# MSP_Telemetry.net
KiCad netlist of a schematic drawn in Altium Designer
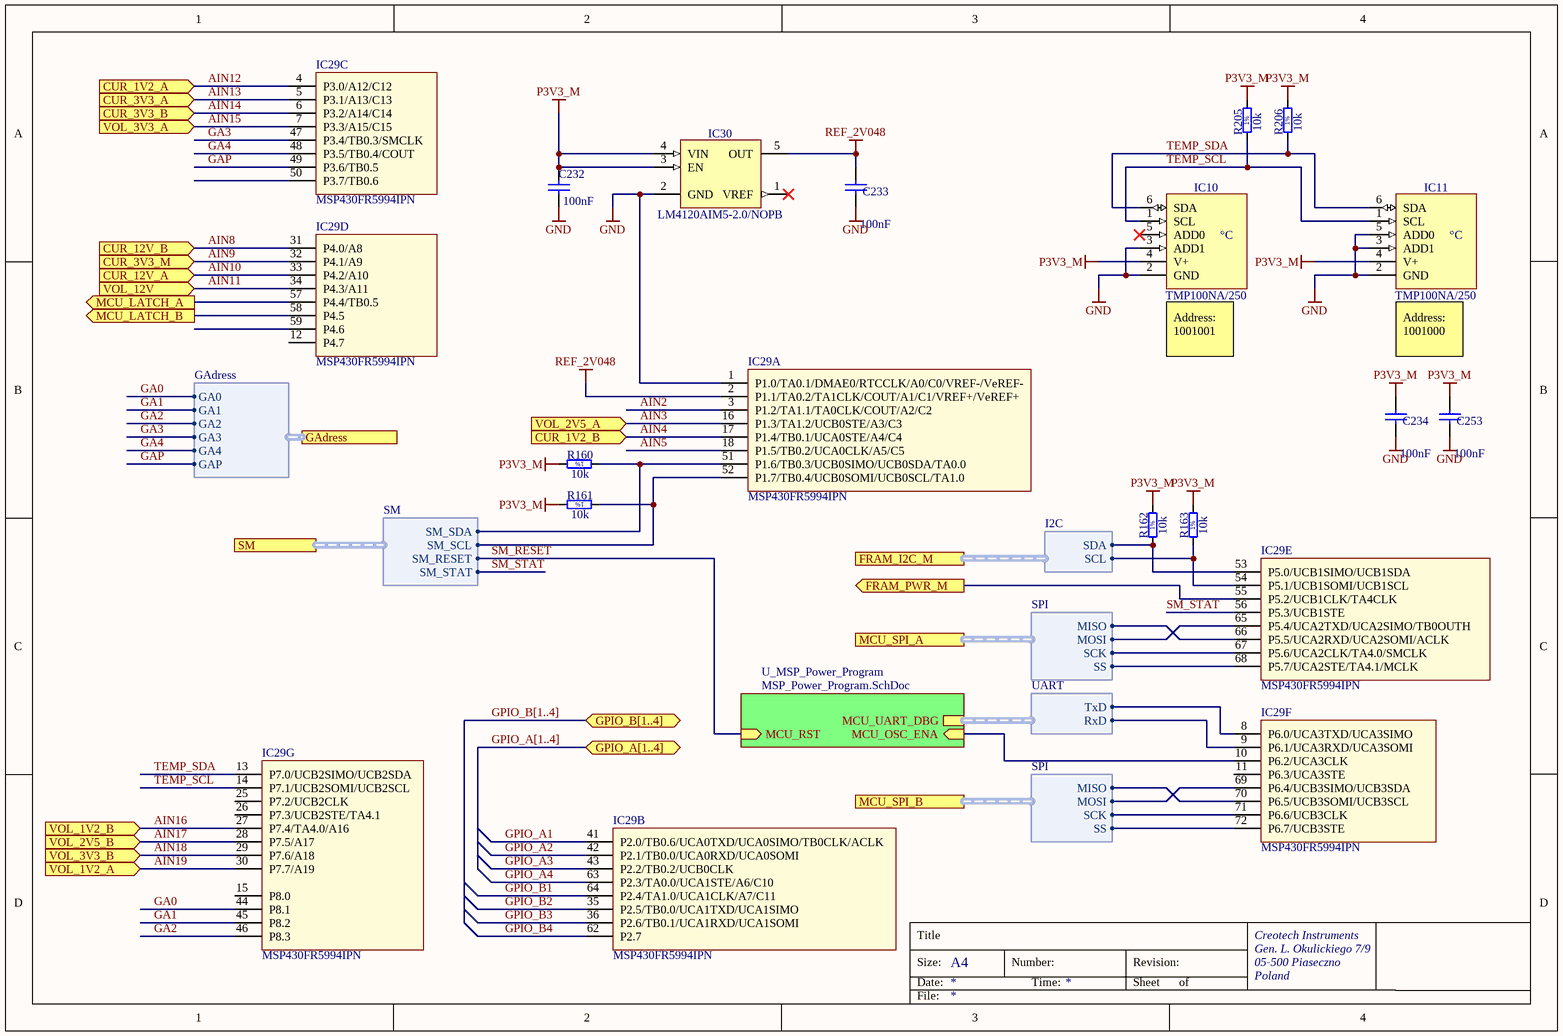
[diagram p0: MSP_Telemetry.SchDoc]

(export (version "E")
  (design (tool "Eeschema 10.0.6"))
  (components
    (comp (ref "C232")
      (value "100nF")
      (footprint "CAPC1608X87N")
      (description "Non-polarised capacitor")
      (fields
        (field (name "PART NUMBER") "CC0603_100NF_50V_10%_X7R")
        (field (name "VOLTAGE") "50V")
        (field (name "AUTHOR") "CERN DEM JLC")
      )
      (libsource (lib "Capacitors") (part "Capacitor - non polarized"))
    )
    (comp (ref "C233")
      (value "100nF")
      (footprint "CAPC1608X87N")
      (description "Non-polarised capacitor")
      (fields
        (field (name "PART NUMBER") "CC0603_100NF_50V_10%_X7R")
        (field (name "VOLTAGE") "50V")
        (field (name "AUTHOR") "CERN DEM JLC")
      )
      (libsource (lib "Capacitors") (part "Capacitor - non polarized"))
    )
    (comp (ref "C234")
      (value "100nF")
      (footprint "CAPC1608X87N")
      (description "Non-polarised capacitor")
      (fields
        (field (name "PART NUMBER") "CC0603_100NF_50V_10%_X7R")
        (field (name "VOLTAGE") "50V")
        (field (name "AUTHOR") "CERN DEM JLC")
      )
      (libsource (lib "Capacitors") (part "Capacitor - non polarized"))
    )
    (comp (ref "C253")
      (value "100nF")
      (footprint "CAPC1608X87N")
      (description "Non-polarised capacitor")
      (fields
        (field (name "PART NUMBER") "CC0603_100NF_50V_10%_X7R")
        (field (name "VOLTAGE") "50V")
        (field (name "AUTHOR") "CERN DEM JLC")
      )
      (libsource (lib "Capacitors") (part "Capacitor - non polarized"))
    )
    (comp (ref "IC10")
      (value "TMP100NA/250")
      (footprint "SOT95P280X145-6N")
      (description "Digital Temperature Sensor with I2C Interface")
      (fields (field (name "MANUFACTURER") "TEXAS INSTRUMENTS") (field (name "AUTHOR") "CERN DEM JLC"))
      (libsource (lib "ICs And Semiconductors") (part "TMP100"))
    )
    (comp (ref "IC11")
      (value "TMP100NA/250")
      (footprint "SOT95P280X145-6N")
      (description "Digital Temperature Sensor with I2C Interface")
      (fields (field (name "MANUFACTURER") "TEXAS INSTRUMENTS") (field (name "AUTHOR") "CERN DEM JLC"))
      (libsource (lib "ICs And Semiconductors") (part "TMP100"))
    )
    (comp (ref "IC29")
      (value "MSP430FR5994IPN")
      (footprint "PQFP50P1400X1400-80N")
      (fields (field (name "MANUFACTURER") "TI"))
      (libsource (lib "LIBRARY_SCH") (part "UPC_MSP430FR5994IPN"))
    )
    (comp (ref "IC30")
      (value "LM4120AIM5-2.0/NOPB")
      (footprint "SOT95P280X145-5N")
      (description "Precision Micropower Low Dropout Voltage Reference")
      (fields (field (name "MANUFACTURER") "TEXAS INSTRUMENTS") (field (name "AUTHOR") "CERN DEM JMW"))
      (libsource (lib "ICs And Semiconductors") (part "LM4120"))
    )
    (comp (ref "R160")
      (value "10k")
      (footprint "RESC1608X55N")
      (description "Resistor - 1%")
      (fields
        (field (name "PART NUMBER") "R0603_10K_1%_0.1W_100PPM")
        (field (name "POWER") "0.1W")
        (field (name "AUTHOR") "CERN DEM JLC")
      )
      (libsource (lib "Resistors") (part "Resistor - 1%"))
    )
    (comp (ref "R161")
      (value "10k")
      (footprint "RESC1608X55N")
      (description "Resistor - 1%")
      (fields
        (field (name "PART NUMBER") "R0603_10K_1%_0.1W_100PPM")
        (field (name "POWER") "0.1W")
        (field (name "AUTHOR") "CERN DEM JLC")
      )
      (libsource (lib "Resistors") (part "Resistor - 1%"))
    )
    (comp (ref "R162")
      (value "10k")
      (footprint "RESC1608X55N")
      (description "Resistor - 1%")
      (fields
        (field (name "PART NUMBER") "R0603_10K_1%_0.1W_100PPM")
        (field (name "POWER") "0.1W")
        (field (name "AUTHOR") "CERN DEM JLC")
      )
      (libsource (lib "Resistors") (part "Resistor - 1%"))
    )
    (comp (ref "R163")
      (value "10k")
      (footprint "RESC1608X55N")
      (description "Resistor - 1%")
      (fields
        (field (name "PART NUMBER") "R0603_10K_1%_0.1W_100PPM")
        (field (name "POWER") "0.1W")
        (field (name "AUTHOR") "CERN DEM JLC")
      )
      (libsource (lib "Resistors") (part "Resistor - 1%"))
    )
    (comp (ref "R205")
      (value "10k")
      (footprint "RESC1608X55N")
      (description "Resistor - 1%")
      (fields
        (field (name "PART NUMBER") "R0603_10K_1%_0.1W_100PPM")
        (field (name "POWER") "0.1W")
        (field (name "AUTHOR") "CERN DEM JLC")
      )
      (libsource (lib "Resistors") (part "Resistor - 1%"))
    )
    (comp (ref "R206")
      (value "10k")
      (footprint "RESC1608X55N")
      (description "Resistor - 1%")
      (fields
        (field (name "PART NUMBER") "R0603_10K_1%_0.1W_100PPM")
        (field (name "POWER") "0.1W")
        (field (name "AUTHOR") "CERN DEM JLC")
      )
      (libsource (lib "Resistors") (part "Resistor - 1%"))
    )
  )
  (nets
    (net (code "6") (name "/AIN2") (class "Default")
      (node (ref "IC29") (pin "3") (pinfunction "P1.2/TA1.1/TA0CLK/COUT/A2/C2_3") (pintype "passive"))
    )
    (net (code "7") (name "/AIN3") (class "Default")
      (node (ref "IC29") (pin "16") (pinfunction "P1.3/TA1.2/UCB0STE/A3/C3_16") (pintype "passive"))
    )
    (net (code "8") (name "/AIN4") (class "Default")
      (node (ref "IC29") (pin "17") (pinfunction "P1.4/TB0.1/UCA0STE/A4/C4_17") (pintype "passive"))
    )
    (net (code "9") (name "/AIN5") (class "Default")
      (node (ref "IC29") (pin "18") (pinfunction "P1.5/TB0.2/UCA0CLK/A5/C5_18") (pintype "passive"))
    )
    (net (code "10") (name "/AIN8") (class "Default")
      (node (ref "IC29") (pin "31") (pinfunction "P4.0/A8_31") (pintype "passive"))
    )
    (net (code "11") (name "/AIN9") (class "Default")
      (node (ref "IC29") (pin "32") (pinfunction "P4.1/A9_32") (pintype "passive"))
    )
    (net (code "12") (name "/AIN10") (class "Default")
      (node (ref "IC29") (pin "33") (pinfunction "P4.2/A10_33") (pintype "passive"))
    )
    (net (code "13") (name "/AIN11") (class "Default")
      (node (ref "IC29") (pin "34") (pinfunction "P4.3/A11_34") (pintype "passive"))
    )
    (net (code "14") (name "/AIN12") (class "Default")
      (node (ref "IC29") (pin "4") (pinfunction "P3.0/A12/C12_4") (pintype "passive"))
    )
    (net (code "15") (name "/AIN13") (class "Default")
      (node (ref "IC29") (pin "5") (pinfunction "P3.1/A13/C13_5") (pintype "passive"))
    )
    (net (code "16") (name "/AIN14") (class "Default")
      (node (ref "IC29") (pin "6") (pinfunction "P3.2/A14/C14_6") (pintype "passive"))
    )
    (net (code "17") (name "/AIN15") (class "Default")
      (node (ref "IC29") (pin "7") (pinfunction "P3.3/A15/C15_7") (pintype "passive"))
    )
    (net (code "18") (name "/AIN16") (class "Default")
      (node (ref "IC29") (pin "27") (pinfunction "P7.4/TA4.0/A16_27") (pintype "passive"))
    )
    (net (code "19") (name "/AIN17") (class "Default")
      (node (ref "IC29") (pin "28") (pinfunction "P7.5/A17_28") (pintype "passive"))
    )
    (net (code "20") (name "/AIN18") (class "Default")
      (node (ref "IC29") (pin "29") (pinfunction "P7.6/A18_29") (pintype "passive"))
    )
    (net (code "21") (name "/AIN19") (class "Default")
      (node (ref "IC29") (pin "30") (pinfunction "P7.7/A19_30") (pintype "passive"))
    )
    (net (code "22") (name "/FRAM_PWR_M") (class "Default")
      (node (ref "IC29") (pin "55") (pinfunction "P5.2/UCB1CLK/TA4CLK_55") (pintype "passive"))
    )
    (net (code "23") (name "/GA0") (class "Default")
      (node (ref "IC29") (pin "44") (pinfunction "P8.1_44") (pintype "passive"))
    )
    (net (code "24") (name "/GA1") (class "Default")
      (node (ref "IC29") (pin "45") (pinfunction "P8.2_45") (pintype "passive"))
    )
    (net (code "25") (name "/GA2") (class "Default")
      (node (ref "IC29") (pin "46") (pinfunction "P8.3_46") (pintype "passive"))
    )
    (net (code "26") (name "/GA3") (class "Default")
      (node (ref "IC29") (pin "47") (pinfunction "P3.4/TB0.3/SMCLK_47") (pintype "passive"))
    )
    (net (code "27") (name "/GA4") (class "Default")
      (node (ref "IC29") (pin "48") (pinfunction "P3.5/TB0.4/COUT_48") (pintype "passive"))
    )
    (net (code "28") (name "/GAP") (class "Default")
      (node (ref "IC29") (pin "49") (pinfunction "P3.6/TB0.5_49") (pintype "passive"))
    )
    (net (code "29") (name "/GPIO_A1") (class "Default")
      (node (ref "IC29") (pin "41") (pinfunction "P2.0/TB0.6/UCA0TXD/UCA0SIMO/TB0CLK/ACLK_41") (pintype "passive"))
    )
    (net (code "30") (name "/GPIO_A2") (class "Default")
      (node (ref "IC29") (pin "42") (pinfunction "P2.1/TB0.0/UCA0RXD/UCA0SOMI_42") (pintype "passive"))
    )
    (net (code "31") (name "/GPIO_A3") (class "Default")
      (node (ref "IC29") (pin "43") (pinfunction "P2.2/TB0.2/UCB0CLK_43") (pintype "passive"))
    )
    (net (code "32") (name "/GPIO_A4") (class "Default")
      (node (ref "IC29") (pin "63") (pinfunction "P2.3/TA0.0/UCA1STE/A6/C10_63") (pintype "passive"))
    )
    (net (code "34") (name "/GPIO_B1") (class "Default")
      (node (ref "IC29") (pin "64") (pinfunction "P2.4/TA1.0/UCA1CLK/A7/C11_64") (pintype "passive"))
    )
    (net (code "35") (name "/GPIO_B2") (class "Default")
      (node (ref "IC29") (pin "35") (pinfunction "P2.5/TB0.0/UCA1TXD/UCA1SIMO_35") (pintype "passive"))
    )
    (net (code "36") (name "/GPIO_B3") (class "Default")
      (node (ref "IC29") (pin "36") (pinfunction "P2.6/TB0.1/UCA1RXD/UCA1SOMI_36") (pintype "passive"))
    )
    (net (code "37") (name "/GPIO_B4") (class "Default")
      (node (ref "IC29") (pin "62") (pinfunction "P2.7_62") (pintype "passive"))
    )
    (net (code "39") (name "/MCU_LATCH_A") (class "Default")
      (node (ref "IC29") (pin "57") (pinfunction "P4.4/TB0.5_57") (pintype "passive"))
    )
    (net (code "40") (name "/MCU_LATCH_B") (class "Default")
      (node (ref "IC29") (pin "58") (pinfunction "P4.5_58") (pintype "passive"))
    )
    (net (code "41") (name "/MCU_OSC_ENA") (class "Default")
      (node (ref "IC29") (pin "10") (pinfunction "P6.2/UCA3CLK_10") (pintype "passive"))
    )
    (net (code "42") (name "/RxD") (class "Default")
      (node (ref "IC29") (pin "9") (pinfunction "P6.1/UCA3RXD/UCA3SOMI_9") (pintype "passive"))
    )
    (net (code "43") (name "/SCL") (class "Default")
      (node (ref "IC29") (pin "54") (pinfunction "P5.1/UCB1SOMI/UCB1SCL_54") (pintype "passive"))
      (node (ref "R163") (pin "1") (pinfunction "1_1") (pintype "passive"))
    )
    (net (code "44") (name "/SDA") (class "Default")
      (node (ref "IC29") (pin "53") (pinfunction "P5.0/UCB1SIMO/UCB1SDA_53") (pintype "passive"))
      (node (ref "R162") (pin "1") (pinfunction "1_1") (pintype "passive"))
    )
    (net (code "46") (name "/SM_SCL") (class "Default")
      (node (ref "IC29") (pin "52") (pinfunction "P1.7/TB0.4/UCB0SOMI/UCB0SCL/TA1.0_52") (pintype "passive"))
      (node (ref "R161") (pin "1") (pinfunction "1_1") (pintype "passive"))
    )
    (net (code "47") (name "/SM_SDA") (class "Default")
      (node (ref "IC29") (pin "51") (pinfunction "P1.6/TB0.3/UCB0SIMO/UCB0SDA/TA0.0_51") (pintype "passive"))
      (node (ref "R160") (pin "1") (pinfunction "1_1") (pintype "passive"))
    )
    (net (code "48") (name "/SM_STAT") (class "Default")
      (node (ref "IC29") (pin "56") (pinfunction "P5.3/UCB1STE_56") (pintype "passive"))
    )
    (net (code "49") (name "/TEMP_SCL") (class "Default")
      (node (ref "IC10") (pin "1") (pinfunction "SCL_1") (pintype "input"))
      (node (ref "IC11") (pin "1") (pinfunction "SCL_1") (pintype "input"))
      (node (ref "IC29") (pin "14") (pinfunction "P7.1/UCB2SOMI/UCB2SCL_14") (pintype "passive"))
      (node (ref "R205") (pin "1") (pinfunction "1_1") (pintype "passive"))
    )
    (net (code "50") (name "/TEMP_SDA") (class "Default")
      (node (ref "IC10") (pin "6") (pinfunction "SDA_6") (pintype "bidirectional"))
      (node (ref "IC11") (pin "6") (pinfunction "SDA_6") (pintype "bidirectional"))
      (node (ref "IC29") (pin "13") (pinfunction "P7.0/UCB2SIMO/UCB2SDA_13") (pintype "passive"))
      (node (ref "R206") (pin "1") (pinfunction "1_1") (pintype "passive"))
    )
    (net (code "51") (name "/TxD") (class "Default")
      (node (ref "IC29") (pin "8") (pinfunction "P6.0/UCA3TXD/UCA3SIMO_8") (pintype "passive"))
    )
    (net (code "57") (name "GND") (class "Default")
      (node (ref "C232") (pin "1") (pinfunction "1_1") (pintype "passive"))
      (node (ref "C233") (pin "1") (pinfunction "1_1") (pintype "passive"))
      (node (ref "C234") (pin "1") (pinfunction "1_1") (pintype "passive"))
      (node (ref "C253") (pin "1") (pinfunction "1_1") (pintype "passive"))
      (node (ref "IC10") (pin "2") (pinfunction "GND_2") (pintype "power_in"))
      (node (ref "IC10") (pin "3") (pinfunction "ADD1_3") (pintype "input"))
      (node (ref "IC11") (pin "2") (pinfunction "GND_2") (pintype "power_in"))
      (node (ref "IC11") (pin "3") (pinfunction "ADD1_3") (pintype "input"))
      (node (ref "IC11") (pin "5") (pinfunction "ADD0_5") (pintype "input"))
      (node (ref "IC29") (pin "1") (pinfunction "P1.0/TA0.1/DMAE0/RTCCLK/A0/C0/VREF-/VeREF-_1") (pintype "passive"))
      (node (ref "IC30") (pin "2") (pinfunction "GND_2") (pintype "power_in"))
    )
    (net (code "58") (name "P3V3_M") (class "Default")
      (node (ref "C232") (pin "2") (pinfunction "2_2") (pintype "passive"))
      (node (ref "C234") (pin "2") (pinfunction "2_2") (pintype "passive"))
      (node (ref "C253") (pin "2") (pinfunction "2_2") (pintype "passive"))
      (node (ref "IC10") (pin "4") (pinfunction "V+_4") (pintype "power_in"))
      (node (ref "IC11") (pin "4") (pinfunction "V+_4") (pintype "power_in"))
      (node (ref "IC30") (pin "3") (pinfunction "EN_3") (pintype "input"))
      (node (ref "IC30") (pin "4") (pinfunction "VIN_4") (pintype "input"))
      (node (ref "R160") (pin "2") (pinfunction "2_2") (pintype "passive"))
      (node (ref "R161") (pin "2") (pinfunction "2_2") (pintype "passive"))
      (node (ref "R162") (pin "2") (pinfunction "2_2") (pintype "passive"))
      (node (ref "R163") (pin "2") (pinfunction "2_2") (pintype "passive"))
      (node (ref "R205") (pin "2") (pinfunction "2_2") (pintype "passive"))
      (node (ref "R206") (pin "2") (pinfunction "2_2") (pintype "passive"))
    )
    (net (code "59") (name "REF_2V048") (class "Default")
      (node (ref "C233") (pin "2") (pinfunction "2_2") (pintype "passive"))
      (node (ref "IC29") (pin "2") (pinfunction "P1.1/TA0.2/TA1CLK/COUT/A1/C1/VREF+/VeREF+_2") (pintype "passive"))
      (node (ref "IC30") (pin "5") (pinfunction "OUT_5") (pintype "power_in"))
    )
    (net (code "60") (name "unconnected-(IC10-ADD0-Pad5)") (class "Default")
      (node (ref "IC10") (pin "5") (pinfunction "ADD0_5") (pintype "input+no_connect"))
    )
    (net (code "61") (name "unconnected-(IC29C-P3.7{slash}TB0.6-Pad50)") (class "Default")
      (node (ref "IC29") (pin "50") (pinfunction "P3.7/TB0.6_50") (pintype "passive"))
    )
    (net (code "62") (name "unconnected-(IC29D-P4.6-Pad59)") (class "Default")
      (node (ref "IC29") (pin "59") (pinfunction "P4.6_59") (pintype "passive"))
    )
    (net (code "63") (name "unconnected-(IC29D-P4.7-Pad12)") (class "Default")
      (node (ref "IC29") (pin "12") (pinfunction "P4.7_12") (pintype "passive"))
    )
    (net (code "64") (name "unconnected-(IC29E-P5.4{slash}UCA2TXD{slash}UCA2SIMO{slash}TB0OUTH-Pad65)") (class "Default")
      (node (ref "IC29") (pin "65") (pinfunction "P5.4/UCA2TXD/UCA2SIMO/TB0OUTH_65") (pintype "passive"))
    )
    (net (code "65") (name "unconnected-(IC29E-P5.5{slash}UCA2RXD{slash}UCA2SOMI{slash}ACLK-Pad66)") (class "Default")
      (node (ref "IC29") (pin "66") (pinfunction "P5.5/UCA2RXD/UCA2SOMI/ACLK_66") (pintype "passive"))
    )
    (net (code "66") (name "unconnected-(IC29E-P5.6{slash}UCA2CLK{slash}TA4.0{slash}SMCLK-Pad67)") (class "Default")
      (node (ref "IC29") (pin "67") (pinfunction "P5.6/UCA2CLK/TA4.0/SMCLK_67") (pintype "passive"))
    )
    (net (code "67") (name "unconnected-(IC29E-P5.7{slash}UCA2STE{slash}TA4.1{slash}MCLK-Pad68)") (class "Default")
      (node (ref "IC29") (pin "68") (pinfunction "P5.7/UCA2STE/TA4.1/MCLK_68") (pintype "passive"))
    )
    (net (code "68") (name "unconnected-(IC29F-P6.3{slash}UCA3STE-Pad11)") (class "Default")
      (node (ref "IC29") (pin "11") (pinfunction "P6.3/UCA3STE_11") (pintype "passive"))
    )
    (net (code "69") (name "unconnected-(IC29F-P6.4{slash}UCB3SIMO{slash}UCB3SDA-Pad69)") (class "Default")
      (node (ref "IC29") (pin "69") (pinfunction "P6.4/UCB3SIMO/UCB3SDA_69") (pintype "passive"))
    )
    (net (code "70") (name "unconnected-(IC29F-P6.5{slash}UCB3SOMI{slash}UCB3SCL-Pad70)") (class "Default")
      (node (ref "IC29") (pin "70") (pinfunction "P6.5/UCB3SOMI/UCB3SCL_70") (pintype "passive"))
    )
    (net (code "71") (name "unconnected-(IC29F-P6.6{slash}UCB3CLK-Pad71)") (class "Default")
      (node (ref "IC29") (pin "71") (pinfunction "P6.6/UCB3CLK_71") (pintype "passive"))
    )
    (net (code "72") (name "unconnected-(IC29F-P6.7{slash}UCB3STE-Pad72)") (class "Default")
      (node (ref "IC29") (pin "72") (pinfunction "P6.7/UCB3STE_72") (pintype "passive"))
    )
    (net (code "73") (name "unconnected-(IC29G-P7.2{slash}UCB2CLK-Pad25)") (class "Default")
      (node (ref "IC29") (pin "25") (pinfunction "P7.2/UCB2CLK_25") (pintype "passive"))
    )
    (net (code "74") (name "unconnected-(IC29G-P7.3{slash}UCB2STE{slash}TA4.1-Pad26)") (class "Default")
      (node (ref "IC29") (pin "26") (pinfunction "P7.3/UCB2STE/TA4.1_26") (pintype "passive"))
    )
    (net (code "75") (name "unconnected-(IC29G-P8.0-Pad15)") (class "Default")
      (node (ref "IC29") (pin "15") (pinfunction "P8.0_15") (pintype "passive"))
    )
    (net (code "76") (name "unconnected-(IC30-VREF-Pad1)") (class "Default")
      (node (ref "IC30") (pin "1") (pinfunction "VREF_1") (pintype "output+no_connect"))
    )
  )
)
